# 5V-DCDC.net
KiCad netlist of a schematic drawn in EAGLE
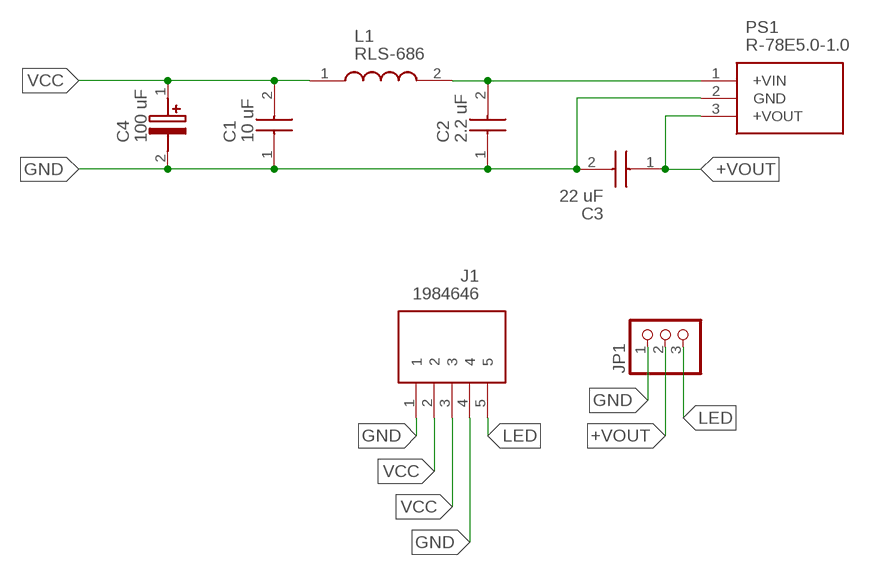
[diagram p0: schematic, sheet 1]

(export (version "E")
  (design (tool "Eeschema 10.0.6"))
  (components
    (comp (ref "C1")
      (value "10 uF")
      (footprint "eagle-import:CAPC3216X180N")
      (fields
        (field (name "MANUFACTURER_PART_NUMBER") "C1206C226M4PACTU")
        (field (name "MOUSER_PART_NUMBER") "80-C1206C226M4P")
      )
      (libsource (lib "eagle-import") (part "C1206C226M4PACTU"))
    )
    (comp (ref "C2")
      (value "2.2 uF")
      (footprint "eagle-import:CAPC3216X180N")
      (fields
        (field (name "MANUFACTURER_PART_NUMBER") "C1206C226M4PACTU")
        (field (name "MOUSER_PART_NUMBER") "80-C1206C226M4P")
      )
      (libsource (lib "eagle-import") (part "C1206C226M4PACTU"))
    )
    (comp (ref "C3")
      (value "22 uF")
      (footprint "eagle-import:CAPC3216X180N")
      (fields
        (field (name "MANUFACTURER_PART_NUMBER") "C1206C226M4PACTU")
        (field (name "MOUSER_PART_NUMBER") "80-C1206C226M4P")
      )
      (libsource (lib "eagle-import") (part "C1206C226M4PACTU"))
    )
    (comp (ref "C4")
      (value "100 uF")
      (footprint "eagle-import:CAPAE660X770N")
      (fields
        (field (name "MANUFACTURER_PART_NUMBER") "865080445010")
        (field (name "MOUSER_PART_NUMBER") "710-865080445010")
      )
      (libsource (lib "eagle-import") (part "865080445010"))
    )
    (comp (ref "J1")
      (value "1984646")
      (footprint "eagle-import:1984646")
      (libsource (lib "eagle-import") (part "1984646"))
    )
    (comp (ref "JP1")
      (value "PINHD-1X3")
      (footprint "eagle-import:1X03")
      (libsource (lib "eagle-import") (part "PINHD-1X3"))
    )
    (comp (ref "L1")
      (value "RLS-686")
      (footprint "eagle-import:RLS686")
      (fields (field (name "MOUSER_PART_NUMBER") "919-RLS-686"))
      (libsource (lib "eagle-import") (part "RLS-686"))
    )
    (comp (ref "PS1")
      (value "R-78E5.0-1.0")
      (footprint "eagle-import:R78E5010")
      (fields (field (name "MOUSER_PART_NUMBER") "919-R-78E5.0-1.0"))
      (libsource (lib "eagle-import") (part "R-78E5.0-1.0"))
    )
  )
  (nets
    (net (code "1") (name "+VOUT") (class "Default")
      (node (ref "C3") (pin "1") (pinfunction "1_1") (pintype "bidirectional"))
      (node (ref "JP1") (pin "2") (pinfunction "2_2") (pintype "passive"))
      (node (ref "PS1") (pin "3") (pinfunction "+VOUT_3") (pintype "bidirectional"))
    )
    (net (code "2") (name "GND") (class "Default")
      (node (ref "C1") (pin "1") (pinfunction "1_1") (pintype "bidirectional"))
      (node (ref "C2") (pin "1") (pinfunction "1_1") (pintype "bidirectional"))
      (node (ref "C3") (pin "2") (pinfunction "2_2") (pintype "bidirectional"))
      (node (ref "C4") (pin "2") (pinfunction "-_2") (pintype "bidirectional"))
      (node (ref "J1") (pin "1") (pinfunction "1_1") (pintype "bidirectional"))
      (node (ref "J1") (pin "4") (pinfunction "4_4") (pintype "bidirectional"))
      (node (ref "JP1") (pin "1") (pinfunction "1_1") (pintype "passive"))
      (node (ref "PS1") (pin "2") (pinfunction "GND_2") (pintype "bidirectional"))
    )
    (net (code "3") (name "LED") (class "Default")
      (node (ref "J1") (pin "5") (pinfunction "5_5") (pintype "bidirectional"))
      (node (ref "JP1") (pin "3") (pinfunction "3_3") (pintype "passive"))
    )
    (net (code "4") (name "Net-(PS1-+VIN)") (class "Default")
      (node (ref "C2") (pin "2") (pinfunction "2_2") (pintype "bidirectional"))
      (node (ref "L1") (pin "2") (pinfunction "2_2") (pintype "bidirectional"))
      (node (ref "PS1") (pin "1") (pinfunction "+VIN_1") (pintype "bidirectional"))
    )
    (net (code "5") (name "VCC") (class "Default")
      (node (ref "C1") (pin "2") (pinfunction "2_2") (pintype "bidirectional"))
      (node (ref "C4") (pin "1") (pinfunction "+_1") (pintype "bidirectional"))
      (node (ref "J1") (pin "2") (pinfunction "2_2") (pintype "bidirectional"))
      (node (ref "J1") (pin "3") (pinfunction "3_3") (pintype "bidirectional"))
      (node (ref "L1") (pin "1") (pinfunction "1_1") (pintype "bidirectional"))
    )
  )
)
